# TC_TouchSwitch.net
KiCad netlist of a schematic drawn in Altium Designer
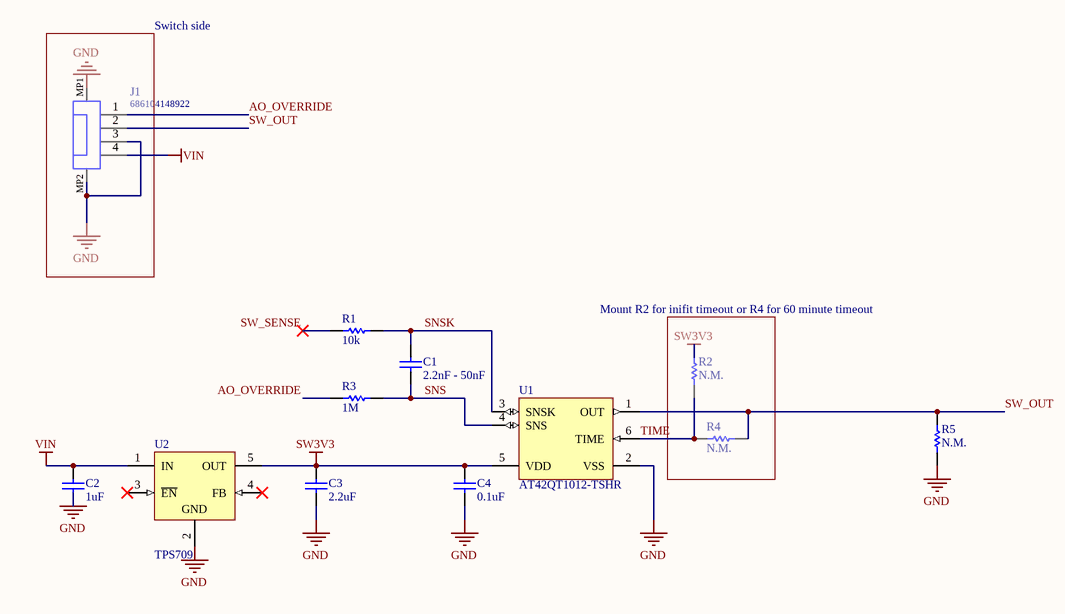
[diagram p0: TC_TouchSwitch.SchDoc]

(export (version "E")
  (design (tool "Eeschema 10.0.6"))
  (components
    (comp (ref "C1")
      (value "2.2nF - 50nF")
      (footprint "CAPC1608X90X35ML10T15")
      (description "Chip Capacitor, 10 nF, +/- 10%, 50 V, -55 to 125 degC, 0603 (1608 Metric), RoHS, Tape and Reel")
      (fields (field (name "VOLTAGE") "50V") (field (name "TOLERANCE") "10%"))
      (libsource (lib "Altium Content Vault") (part "CAP-NP-2"))
    )
    (comp (ref "C2")
      (value "1uF")
      (footprint "CAPC1608X90X20LL10")
      (description "Chip Capacitor, 1 uF, +/- 10%, 50 V, -55 to 85 degC, 0603 (1608 Metric), RoHS, Tape and Reel")
      (fields
        (field (name "MANUFACTURER") "TDK")
        (field (name "PCN PART NUMBER") "MLCCPartNumberChange30/Nov/2012")
      )
      (libsource (lib "Altium Content Vault") (part "CAP-NP-2"))
    )
    (comp (ref "C3")
      (value "2.2uF")
      (footprint "CAPC1608X90X35ML10T15")
      (fields (field (name "MANUFACTURER") "Murata") (field (name "PART NUMBER") "GRM188R71A225KE15D"))
      (libsource (lib "Altium Content Vault") (part "CAP"))
    )
    (comp (ref "C4")
      (value "0.1uF")
      (footprint "CAPC1608X87X35NL15T15")
      (fields (field (name "PART NUMBER") "C0603X104K5RACTU") (field (name "MANUFACTURER") "Kemet"))
      (libsource (lib "Altium Content Vault") (part "CAP"))
    )
    (comp (ref "J1")
      (value "686104148922")
      (footprint "686104148922")
      (description "SMT ZIF Connectors Hinge Type WR-FPC, Horizontal, Bottom Contact, pitch 1 mm, 4 pins")
      (fields (field (name "MANUFACTURER") "Wurth Elektronik") (field (name "PUBLISHER") "WurthElektronik"))
      (libsource (lib "Altium Content Vault") (part "WE-6861041XXX22-4"))
    )
    (comp (ref "R1")
      (value "10k")
      (footprint "RESC1609X55X30LL15T15")
      (description "Chip Resistor, 10 KOhm, +/- 1%, 0.1 W, -55 to 155 degC, 0603 (1608 Metric), RoHS, Tape and Reel")
      (fields (field (name "TOLERANCE") "1%") (field (name "MANUFACTURER") "Panasonic"))
      (libsource (lib "Altium Content Vault") (part "RES-2"))
    )
    (comp (ref "R2")
      (value "N.M.")
      (footprint "RESC1608X55X25ML10T15")
      (description "Chip Resistor, 100 KOhm, +/- 1%, 0.1 W, -55 to 155 degC, 0603 (1608 Metric), RoHS, Tape and Reel")
      (fields (field (name "MANUFACTURER") "Yageo") (field (name "TOLERANCE") "1%"))
      (libsource (lib "Altium Content Vault") (part "RES-2"))
    )
    (comp (ref "R3")
      (value "1M")
      (footprint "RESC1609X50X30LL10T20")
      (fields (field (name "MANUFACTURER") "Vishay Dale") (field (name "PART NUMBER") "CRCW06031M00FKEA"))
      (libsource (lib "Altium Content Vault") (part "RES"))
    )
    (comp (ref "R4")
      (value "N.M.")
      (footprint "RESC1608X55X25ML10T15")
      (description "Chip Resistor, 100 KOhm, +/- 1%, 0.1 W, -55 to 155 degC, 0603 (1608 Metric), RoHS, Tape and Reel")
      (fields (field (name "MANUFACTURER") "Yageo") (field (name "TOLERANCE") "1%"))
      (libsource (lib "Altium Content Vault") (part "RES-2"))
    )
    (comp (ref "R5")
      (value "N.M.")
      (footprint "RESC1608X55X25ML10T15")
      (description "Chip Resistor, 100 KOhm, +/- 1%, 0.1 W, -55 to 155 degC, 0603 (1608 Metric), RoHS, Tape and Reel")
      (fields (field (name "MANUFACTURER") "Yageo") (field (name "TOLERANCE") "1%"))
      (libsource (lib "Altium Content Vault") (part "RES-2"))
    )
    (comp (ref "U1")
      (value "AT42QT1012-TSHR")
      (footprint "6ST1_M")
      (libsource (lib "Altium Content Vault") (part "IN-TSC-AT42QT1012-6"))
    )
    (comp (ref "U2")
      (value "TPS709")
      (footprint "DBV0005A_M")
      (fields (field (name "PARTNUMBER") "TPS76901DBVR") (field (name "MANUFACTURER") "Texas Instruments"))
      (libsource (lib "Altium Content Vault") (part "TI-TPS7XX01-DBV5"))
    )
  )
  (nets
    (net (code "1") (name "/AO_OVERRIDE") (class "Default")
      (node (ref "J1") (pin "1") (pinfunction "1_1") (pintype "passive"))
      (node (ref "R3") (pin "2") (pinfunction "2_2") (pintype "passive"))
    )
    (net (code "2") (name "/SNS") (class "Default")
      (node (ref "C1") (pin "1") (pinfunction "1_1") (pintype "passive"))
      (node (ref "R3") (pin "1") (pinfunction "1_1") (pintype "passive"))
      (node (ref "U1") (pin "4") (pinfunction "SNS_4") (pintype "bidirectional"))
    )
    (net (code "3") (name "/SNSK") (class "Default")
      (node (ref "C1") (pin "2") (pinfunction "2_2") (pintype "passive"))
      (node (ref "R1") (pin "2") (pinfunction "2_2") (pintype "passive"))
      (node (ref "U1") (pin "3") (pinfunction "SNSK_3") (pintype "bidirectional"))
    )
    (net (code "4") (name "/SW_OUT") (class "Default")
      (node (ref "J1") (pin "2") (pinfunction "2_2") (pintype "passive"))
      (node (ref "R4") (pin "1") (pinfunction "1_1") (pintype "passive"))
      (node (ref "R5") (pin "2") (pinfunction "2_2") (pintype "passive"))
      (node (ref "U1") (pin "1") (pinfunction "OUT_1") (pintype "output"))
    )
    (net (code "5") (name "/SW_SENSE") (class "Default")
      (node (ref "R1") (pin "1") (pinfunction "1_1") (pintype "passive+no_connect"))
    )
    (net (code "6") (name "/TIME") (class "Default")
      (node (ref "R2") (pin "1") (pinfunction "1_1") (pintype "passive"))
      (node (ref "R4") (pin "2") (pinfunction "2_2") (pintype "passive"))
      (node (ref "U1") (pin "6") (pinfunction "TIME_6") (pintype "input"))
    )
    (net (code "7") (name "GND") (class "Default")
      (node (ref "C2") (pin "1") (pinfunction "1_1") (pintype "passive"))
      (node (ref "C3") (pin "1") (pinfunction "1_1") (pintype "passive"))
      (node (ref "C4") (pin "2") (pinfunction "2_2") (pintype "passive"))
      (node (ref "J1") (pin "3") (pinfunction "3_3") (pintype "passive"))
      (node (ref "J1") (pin "MP1") (pinfunction "MP1_MP1") (pintype "passive"))
      (node (ref "J1") (pin "MP2") (pinfunction "MP2_MP2") (pintype "passive"))
      (node (ref "R5") (pin "1") (pinfunction "1_1") (pintype "passive"))
      (node (ref "U1") (pin "2") (pinfunction "VSS_2") (pintype "power_in"))
      (node (ref "U2") (pin "2") (pinfunction "GND_2") (pintype "power_in"))
    )
    (net (code "8") (name "SW3V3") (class "Default")
      (node (ref "C3") (pin "2") (pinfunction "2_2") (pintype "passive"))
      (node (ref "C4") (pin "1") (pinfunction "1_1") (pintype "passive"))
      (node (ref "R2") (pin "2") (pinfunction "2_2") (pintype "passive"))
      (node (ref "U1") (pin "5") (pinfunction "VDD_5") (pintype "power_in"))
      (node (ref "U2") (pin "5") (pinfunction "OUT_5") (pintype "power_in"))
    )
    (net (code "9") (name "VIN") (class "Default")
      (node (ref "C2") (pin "2") (pinfunction "2_2") (pintype "passive"))
      (node (ref "J1") (pin "4") (pinfunction "4_4") (pintype "passive"))
      (node (ref "U2") (pin "1") (pinfunction "IN_1") (pintype "power_in"))
    )
    (net (code "10") (name "unconnected-(U2-FB-Pad4)") (class "Default")
      (node (ref "U2") (pin "4") (pinfunction "FB_4") (pintype "input+no_connect"))
    )
    (net (code "11") (name "unconnected-(U2-~{EN}-Pad3)") (class "Default")
      (node (ref "U2") (pin "3") (pinfunction "~{EN}_3") (pintype "input+no_connect"))
    )
  )
)
